# decoder.net
KiCad netlist of a schematic drawn in Altium Designer
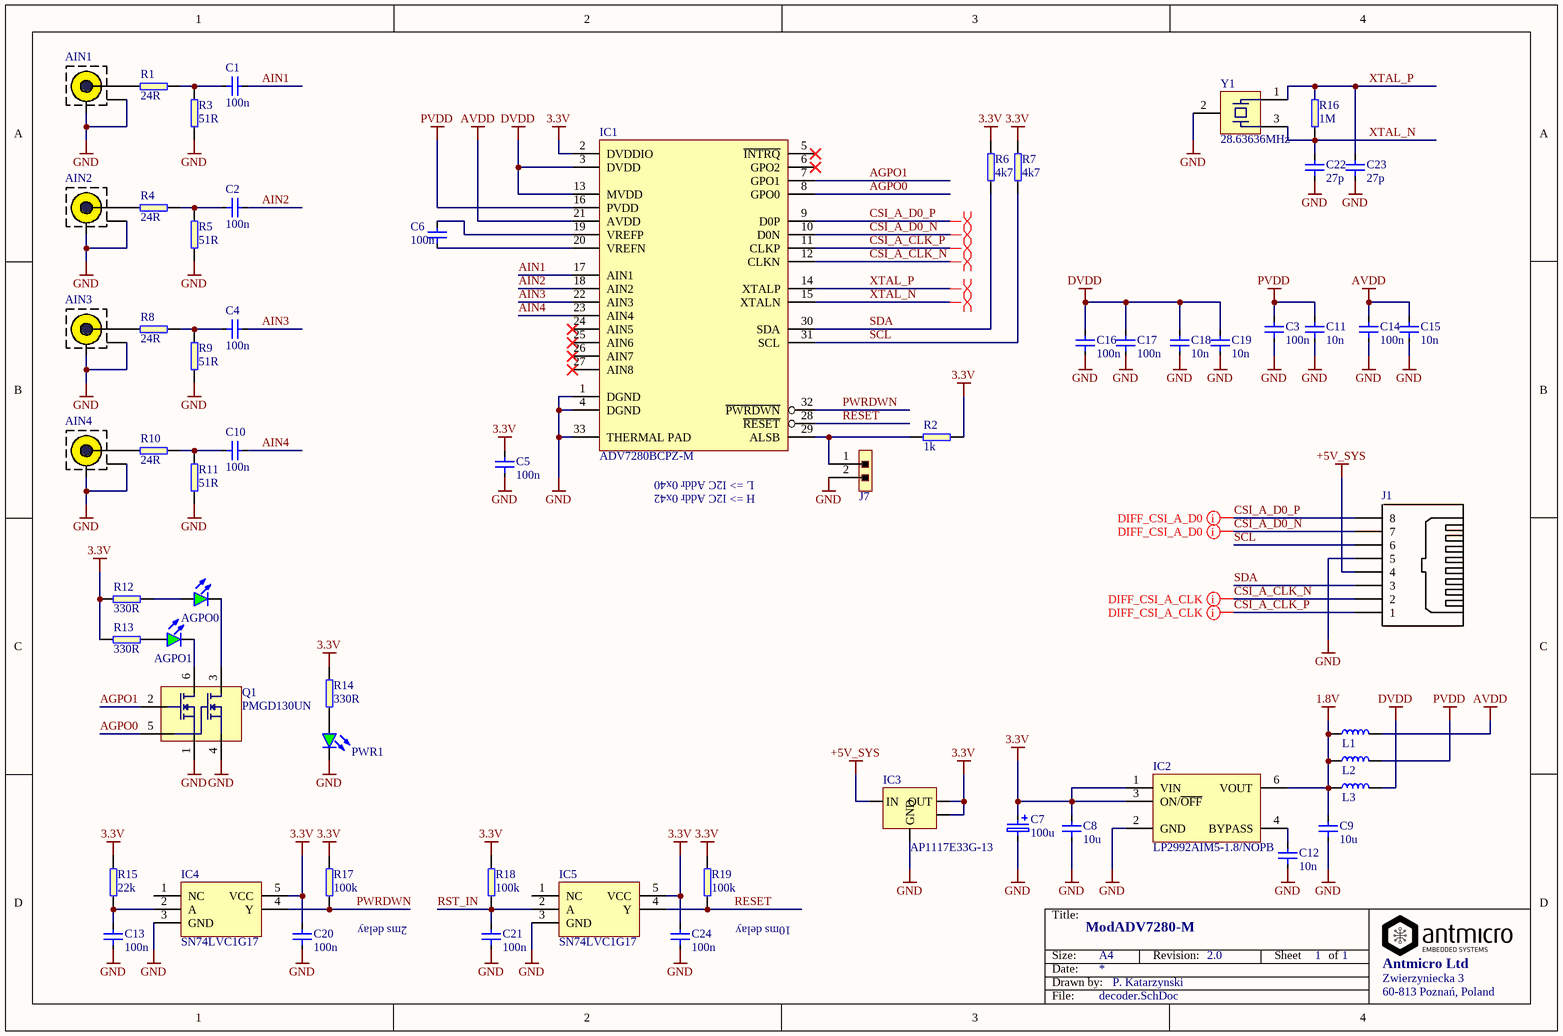
[diagram p0: decoder.SchDoc]

(export (version "E")
  (design (tool "Eeschema 10.0.6"))
  (components
    (comp (ref "AGPO0")
      (value "*")
      (footprint "LED0603")
      (description "LED Green 0603 case")
      (fields (field (name "PART NUMBER") "LED_G"))
      (libsource (lib "AntmicroComponents") (part "LED"))
    )
    (comp (ref "AGPO1")
      (value "*")
      (footprint "LED0603")
      (description "LED Green 0603 case")
      (fields (field (name "PART NUMBER") "LED_G"))
      (libsource (lib "AntmicroComponents") (part "LED"))
    )
    (comp (ref "AIN1")
      (value "~")
      (footprint "CC-134B")
      (description "Shielded RCA socket")
      (fields (field (name "PART NUMBER") "CC-134B"))
      (libsource (lib "AntmicroComponents") (part "CC-134B"))
    )
    (comp (ref "AIN2")
      (value "~")
      (footprint "CC-134B")
      (description "Shielded RCA socket")
      (fields (field (name "PART NUMBER") "CC-134B"))
      (libsource (lib "AntmicroComponents") (part "CC-134B"))
    )
    (comp (ref "AIN3")
      (value "~")
      (footprint "CC-134B")
      (description "Shielded RCA socket")
      (fields (field (name "PART NUMBER") "CC-134B"))
      (libsource (lib "AntmicroComponents") (part "CC-134B"))
    )
    (comp (ref "AIN4")
      (value "~")
      (footprint "CC-134B")
      (description "Shielded RCA socket")
      (fields (field (name "PART NUMBER") "CC-134B"))
      (libsource (lib "AntmicroComponents") (part "CC-134B"))
    )
    (comp (ref "C1")
      (value "100n")
      (footprint "0603")
      (description "MLCC SMT Capacitor 100nF 0603")
      (fields (field (name "PART NUMBER") "C_100n_0603") (field (name "TOLERANCE") "5%"))
      (libsource (lib "AntmicroComponents") (part "C"))
    )
    (comp (ref "C2")
      (value "100n")
      (footprint "0603")
      (description "MLCC SMT Capacitor 100nF 0603")
      (fields (field (name "PART NUMBER") "C_100n_0603") (field (name "TOLERANCE") "5%"))
      (libsource (lib "AntmicroComponents") (part "C"))
    )
    (comp (ref "C3")
      (value "100n")
      (footprint "0603")
      (description "MLCC SMT Capacitor 100nF 0603")
      (fields (field (name "PART NUMBER") "C_100n_0603") (field (name "TOLERANCE") "5%"))
      (libsource (lib "AntmicroComponents") (part "C"))
    )
    (comp (ref "C4")
      (value "100n")
      (footprint "0603")
      (description "MLCC SMT Capacitor 100nF 0603")
      (fields (field (name "PART NUMBER") "C_100n_0603") (field (name "TOLERANCE") "5%"))
      (libsource (lib "AntmicroComponents") (part "C"))
    )
    (comp (ref "C5")
      (value "100n")
      (footprint "0603")
      (description "MLCC SMT Capacitor 100nF 0603")
      (fields (field (name "PART NUMBER") "C_100n_0603") (field (name "TOLERANCE") "5%"))
      (libsource (lib "AntmicroComponents") (part "C"))
    )
    (comp (ref "C6")
      (value "100n")
      (footprint "0603")
      (description "MLCC SMT Capacitor 100nF 0603")
      (fields (field (name "PART NUMBER") "C_100n_0603") (field (name "TOLERANCE") "5%"))
      (libsource (lib "AntmicroComponents") (part "C"))
    )
    (comp (ref "C7")
      (value "100u")
      (footprint "KEMET_A")
      (description "Tantalum SMT Capacitor 100uF Case KEMET_A")
      (fields (field (name "PART NUMBER") "C_100u_KEMET_A"))
      (libsource (lib "AntmicroComponents") (part "CPol"))
    )
    (comp (ref "C8")
      (value "10u")
      (footprint "0603")
      (description "MLCC SMT Capacitor 10uF 0603")
      (fields (field (name "PART NUMBER") "C_10u_0603"))
      (libsource (lib "AntmicroComponents") (part "C"))
    )
    (comp (ref "C9")
      (value "10u")
      (footprint "0603")
      (description "MLCC SMT Capacitor 10uF 0603")
      (fields (field (name "PART NUMBER") "C_10u_0603"))
      (libsource (lib "AntmicroComponents") (part "C"))
    )
    (comp (ref "C10")
      (value "100n")
      (footprint "0603")
      (description "MLCC SMT Capacitor 100nF 0603")
      (fields (field (name "PART NUMBER") "C_100n_0603") (field (name "TOLERANCE") "5%"))
      (libsource (lib "AntmicroComponents") (part "C"))
    )
    (comp (ref "C11")
      (value "10n")
      (footprint "0603")
      (description "MLCC SMT Capacitor 10nF 0603")
      (fields (field (name "PART NUMBER") "C_10n_0603"))
      (libsource (lib "AntmicroComponents") (part "C"))
    )
    (comp (ref "C12")
      (value "10n")
      (footprint "0603")
      (description "MLCC SMT Capacitor 10nF 0603")
      (fields (field (name "PART NUMBER") "C_10n_0603"))
      (libsource (lib "AntmicroComponents") (part "C"))
    )
    (comp (ref "C13")
      (value "100n")
      (footprint "0603")
      (description "MLCC SMT Capacitor 100nF 0603")
      (fields (field (name "PART NUMBER") "C_100n_0603") (field (name "TOLERANCE") "5%"))
      (libsource (lib "AntmicroComponents") (part "C"))
    )
    (comp (ref "C14")
      (value "100n")
      (footprint "0603")
      (description "MLCC SMT Capacitor 100nF 0603")
      (fields (field (name "PART NUMBER") "C_100n_0603") (field (name "TOLERANCE") "5%"))
      (libsource (lib "AntmicroComponents") (part "C"))
    )
    (comp (ref "C15")
      (value "10n")
      (footprint "0603")
      (description "MLCC SMT Capacitor 10nF 0603")
      (fields (field (name "PART NUMBER") "C_10n_0603"))
      (libsource (lib "AntmicroComponents") (part "C"))
    )
    (comp (ref "C16")
      (value "100n")
      (footprint "0603")
      (description "MLCC SMT Capacitor 100nF 0603")
      (fields (field (name "PART NUMBER") "C_100n_0603") (field (name "TOLERANCE") "5%"))
      (libsource (lib "AntmicroComponents") (part "C"))
    )
    (comp (ref "C17")
      (value "100n")
      (footprint "0603")
      (description "MLCC SMT Capacitor 100nF 0603")
      (fields (field (name "PART NUMBER") "C_100n_0603") (field (name "TOLERANCE") "5%"))
      (libsource (lib "AntmicroComponents") (part "C"))
    )
    (comp (ref "C18")
      (value "10n")
      (footprint "0603")
      (description "MLCC SMT Capacitor 10nF 0603")
      (fields (field (name "PART NUMBER") "C_10n_0603"))
      (libsource (lib "AntmicroComponents") (part "C"))
    )
    (comp (ref "C19")
      (value "10n")
      (footprint "0603")
      (description "MLCC SMT Capacitor 10nF 0603")
      (fields (field (name "PART NUMBER") "C_10n_0603"))
      (libsource (lib "AntmicroComponents") (part "C"))
    )
    (comp (ref "C20")
      (value "100n")
      (footprint "0603")
      (description "MLCC SMT Capacitor 100nF 0603")
      (fields (field (name "PART NUMBER") "C_100n_0603") (field (name "TOLERANCE") "5%"))
      (libsource (lib "AntmicroComponents") (part "C"))
    )
    (comp (ref "C21")
      (value "100n")
      (footprint "0603")
      (description "MLCC SMT Capacitor 100nF 0603")
      (fields (field (name "PART NUMBER") "C_100n_0603") (field (name "TOLERANCE") "5%"))
      (libsource (lib "AntmicroComponents") (part "C"))
    )
    (comp (ref "C22")
      (value "27p")
      (footprint "0603")
      (description "MLCC SMT Capacitor 27pF 0603")
      (fields (field (name "PART NUMBER") "C_27p_0603"))
      (libsource (lib "AntmicroComponents") (part "C"))
    )
    (comp (ref "C23")
      (value "27p")
      (footprint "0603")
      (description "MLCC SMT Capacitor 27pF 0603")
      (fields (field (name "PART NUMBER") "C_27p_0603"))
      (libsource (lib "AntmicroComponents") (part "C"))
    )
    (comp (ref "C24")
      (value "100n")
      (footprint "0603")
      (description "MLCC SMT Capacitor 100nF 0603")
      (fields (field (name "PART NUMBER") "C_100n_0603") (field (name "TOLERANCE") "5%"))
      (libsource (lib "AntmicroComponents") (part "C"))
    )
    (comp (ref "IC1")
      (value "ADV7280BCPZ-M")
      (footprint "LFCSP-32")
      (description "MIPI 10Bit 4x Oversampled SDTV Video Decoder with Deinterlacer")
      (libsource (lib "AntmicroComponents") (part "ADV7280-M"))
    )
    (comp (ref "IC2")
      (value "LP2992AIM5-1.8/NOPB")
      (footprint "SOT23-5N")
      (description "LDO 1.8V 250mA")
      (fields (field (name "PART NUMBER") "LP2992AIM5-1.8"))
      (libsource (lib "AntmicroComponents") (part "LP2992AIM5-1.8"))
    )
    (comp (ref "IC3")
      (value "AP1117E33G-13")
      (footprint "SOT223")
      (description "IC, LDO, REG, 3.3V, SOT223")
      (libsource (lib "AntmicroComponents") (part "xx1117"))
    )
    (comp (ref "IC4")
      (value "SN74LVC1G17")
      (footprint "SOT23127P600-8N")
      (description "Single Schmitt trigger buffer")
      (libsource (lib "AntmicroComponents") (part "SN74LVC1G17"))
    )
    (comp (ref "IC5")
      (value "SN74LVC1G17")
      (footprint "SOT23127P600-8N")
      (description "Single Schmitt trigger buffer")
      (libsource (lib "AntmicroComponents") (part "SN74LVC1G17"))
    )
    (comp (ref "J1")
      (value "~")
      (footprint "RJ45 AMP-1-406541")
      (description "MODULAR, JACK, THT, R/A, RJ45, 8P8C")
      (fields (field (name "PART NUMBER") "RJ45 AMP-1-406541"))
      (libsource (lib "AntmicroComponents") (part "RJ45 AMP-1-406541"))
    )
    (comp (ref "J7")
      (value "*")
      (footprint "HEADER_1X2_male 2.54mm")
      (description "1x2 pinhead male")
      (fields (field (name "PART NUMBER") "HEADER_1X2_male"))
      (libsource (lib "AntmicroComponents") (part "HEADER_1X2_male"))
    )
    (comp (ref "L1")
      (value "*")
      (footprint "0805")
      (description "WURTH ELEKTRONIK - 742792022 - FERRITE BEAD, 0.05OHM, 2A, 0805")
      (fields (field (name "PART NUMBER") "742792022") (field (name "TOLERANCE") "25%"))
      (libsource (lib "AntmicroComponents") (part "Inductor SMT"))
    )
    (comp (ref "L2")
      (value "*")
      (footprint "0805")
      (description "WURTH ELEKTRONIK - 742792022 - FERRITE BEAD, 0.05OHM, 2A, 0805")
      (fields (field (name "PART NUMBER") "742792022") (field (name "TOLERANCE") "25%"))
      (libsource (lib "AntmicroComponents") (part "Inductor SMT"))
    )
    (comp (ref "L3")
      (value "*")
      (footprint "0805")
      (description "WURTH ELEKTRONIK - 742792022 - FERRITE BEAD, 0.05OHM, 2A, 0805")
      (fields (field (name "PART NUMBER") "742792022") (field (name "TOLERANCE") "25%"))
      (libsource (lib "AntmicroComponents") (part "Inductor SMT"))
    )
    (comp (ref "PWR1")
      (value "*")
      (footprint "LED0603")
      (description "LED Green 0603 case")
      (fields (field (name "PART NUMBER") "LED_G"))
      (libsource (lib "AntmicroComponents") (part "LED"))
    )
    (comp (ref "Q1")
      (value "PMGD130UN")
      (footprint "TSOP65P210X110-6N")
      (description "20 V, dual N-channel Trench MOSFET")
      (libsource (lib "AntmicroComponents") (part "PMGD130UN"))
    )
    (comp (ref "R1")
      (value "24R")
      (footprint "0603")
      (description "SMT Resistor 24R 0603")
      (fields (field (name "PART NUMBER") "R_24R_0603"))
      (libsource (lib "") (part "R_1"))
    )
    (comp (ref "R2")
      (value "1k")
      (footprint "0603")
      (description "SMT Resistor 1k 0603")
      (fields (field (name "PART NUMBER") "R_1k_0603") (field (name "TOLERANCE") "5%"))
      (libsource (lib "") (part "R_2"))
    )
    (comp (ref "R3")
      (value "51R")
      (footprint "0805")
      (description "SMT Resistor 51R 0805")
      (fields (field (name "PART NUMBER") "R_51R_0805") (field (name "TOLERANCE") "1%"))
      (libsource (lib "AntmicroComponents") (part "R"))
    )
    (comp (ref "R4")
      (value "24R")
      (footprint "0603")
      (description "SMT Resistor 24R 0603")
      (fields (field (name "PART NUMBER") "R_24R_0603"))
      (libsource (lib "") (part "R_1"))
    )
    (comp (ref "R5")
      (value "51R")
      (footprint "0805")
      (description "SMT Resistor 51R 0805")
      (fields (field (name "PART NUMBER") "R_51R_0805") (field (name "TOLERANCE") "1%"))
      (libsource (lib "AntmicroComponents") (part "R"))
    )
    (comp (ref "R6")
      (value "4k7")
      (footprint "0603")
      (description "SMT Resistor 4k7 0603")
      (fields (field (name "PART NUMBER") "R_4k7_0603"))
      (libsource (lib "AntmicroComponents") (part "R"))
    )
    (comp (ref "R7")
      (value "4k7")
      (footprint "0603")
      (description "SMT Resistor 4k7 0603")
      (fields (field (name "PART NUMBER") "R_4k7_0603"))
      (libsource (lib "AntmicroComponents") (part "R"))
    )
    (comp (ref "R8")
      (value "24R")
      (footprint "0603")
      (description "SMT Resistor 24R 0603")
      (fields (field (name "PART NUMBER") "R_24R_0603"))
      (libsource (lib "") (part "R_1"))
    )
    (comp (ref "R9")
      (value "51R")
      (footprint "0805")
      (description "SMT Resistor 51R 0805")
      (fields (field (name "PART NUMBER") "R_51R_0805") (field (name "TOLERANCE") "1%"))
      (libsource (lib "AntmicroComponents") (part "R"))
    )
    (comp (ref "R10")
      (value "24R")
      (footprint "0603")
      (description "SMT Resistor 24R 0603")
      (fields (field (name "PART NUMBER") "R_24R_0603"))
      (libsource (lib "") (part "R_1"))
    )
    (comp (ref "R11")
      (value "51R")
      (footprint "0805")
      (description "SMT Resistor 51R 0805")
      (fields (field (name "PART NUMBER") "R_51R_0805") (field (name "TOLERANCE") "1%"))
      (libsource (lib "AntmicroComponents") (part "R"))
    )
    (comp (ref "R12")
      (value "330R")
      (footprint "0603")
      (description "SMT Resistor 330R 0603")
      (fields (field (name "PART NUMBER") "R_330R_0603") (field (name "TOLERANCE") "5%"))
      (libsource (lib "") (part "R_2"))
    )
    (comp (ref "R13")
      (value "330R")
      (footprint "0603")
      (description "SMT Resistor 330R 0603")
      (fields (field (name "PART NUMBER") "R_330R_0603") (field (name "TOLERANCE") "5%"))
      (libsource (lib "") (part "R_2"))
    )
    (comp (ref "R14")
      (value "330R")
      (footprint "0603")
      (description "SMT Resistor 330R 0603")
      (fields (field (name "PART NUMBER") "R_330R_0603") (field (name "TOLERANCE") "5%"))
      (libsource (lib "AntmicroComponents") (part "R"))
    )
    (comp (ref "R15")
      (value "22k")
      (footprint "0603")
      (description "SMT Resistor 22k 0603")
      (fields (field (name "PART NUMBER") "R_22k_0603"))
      (libsource (lib "AntmicroComponents") (part "R"))
    )
    (comp (ref "R16")
      (value "1M")
      (footprint "0603")
      (description "SMT Resistor 1M 0603")
      (fields (field (name "PART NUMBER") "R_1M_0603"))
      (libsource (lib "AntmicroComponents") (part "R"))
    )
    (comp (ref "R17")
      (value "100k")
      (footprint "0603")
      (description "SMT Resistor 100k 0603")
      (fields (field (name "PART NUMBER") "R_100k_0603") (field (name "TOLERANCE") "5%"))
      (libsource (lib "AntmicroComponents") (part "R"))
    )
    (comp (ref "R18")
      (value "100k")
      (footprint "0603")
      (description "SMT Resistor 100k 0603")
      (fields (field (name "PART NUMBER") "R_100k_0603") (field (name "TOLERANCE") "5%"))
      (libsource (lib "AntmicroComponents") (part "R"))
    )
    (comp (ref "R19")
      (value "100k")
      (footprint "0603")
      (description "SMT Resistor 100k 0603")
      (fields (field (name "PART NUMBER") "R_100k_0603") (field (name "TOLERANCE") "5%"))
      (libsource (lib "AntmicroComponents") (part "R"))
    )
    (comp (ref "Y1")
      (value "28.63636MHz")
      (footprint "TXC_7B")
      (description "TXC  7B-28.63636MAAJ-T  XTAL, 28.63636MHZ, 18PF, SMD, 5X3.2")
      (fields (field (name "PART NUMBER") "7B-28.63636MAAJ-T"))
      (libsource (lib "AntmicroComponents") (part "TXC_7B"))
    )
  )
  (nets
    (net (code "1") (name "+5V_SYS") (class "Default")
      (node (ref "IC3") (pin "3") (pinfunction "IN_3") (pintype "power_in"))
      (node (ref "J1") (pin "4") (pinfunction "4_4") (pintype "passive"))
    )
    (net (code "2") (name "/AGPO0") (class "Default")
      (node (ref "IC1") (pin "8") (pinfunction "GPO0_8") (pintype "passive"))
      (node (ref "Q1") (pin "5") (pinfunction "G2_5") (pintype "passive"))
    )
    (net (code "3") (name "/AGPO1") (class "Default")
      (node (ref "IC1") (pin "7") (pinfunction "GPO1_7") (pintype "passive"))
      (node (ref "Q1") (pin "2") (pinfunction "G1_2") (pintype "passive"))
    )
    (net (code "4") (name "/AIN1") (class "Default")
      (node (ref "C1") (pin "2") (pinfunction "2_2") (pintype "passive"))
      (node (ref "IC1") (pin "17") (pinfunction "AIN1_17") (pintype "passive"))
    )
    (net (code "5") (name "/AIN2") (class "Default")
      (node (ref "C2") (pin "2") (pinfunction "2_2") (pintype "passive"))
      (node (ref "IC1") (pin "18") (pinfunction "AIN2_18") (pintype "passive"))
    )
    (net (code "6") (name "/AIN3") (class "Default")
      (node (ref "C4") (pin "2") (pinfunction "2_2") (pintype "passive"))
      (node (ref "IC1") (pin "22") (pinfunction "AIN3_22") (pintype "passive"))
    )
    (net (code "7") (name "/AIN4") (class "Default")
      (node (ref "C10") (pin "2") (pinfunction "2_2") (pintype "passive"))
      (node (ref "IC1") (pin "23") (pinfunction "AIN4_23") (pintype "passive"))
    )
    (net (code "8") (name "/CSI_A_CLK_N") (class "Default")
      (node (ref "IC1") (pin "12") (pinfunction "CLKN_12") (pintype "passive"))
      (node (ref "J1") (pin "2") (pinfunction "2_2") (pintype "passive"))
    )
    (net (code "9") (name "/CSI_A_CLK_P") (class "Default")
      (node (ref "IC1") (pin "11") (pinfunction "CLKP_11") (pintype "passive"))
      (node (ref "J1") (pin "1") (pinfunction "1_1") (pintype "passive"))
    )
    (net (code "10") (name "/CSI_A_D0_N") (class "Default")
      (node (ref "IC1") (pin "10") (pinfunction "D0N_10") (pintype "passive"))
      (node (ref "J1") (pin "7") (pinfunction "7_7") (pintype "passive"))
    )
    (net (code "11") (name "/CSI_A_D0_P") (class "Default")
      (node (ref "IC1") (pin "9") (pinfunction "D0P_9") (pintype "passive"))
      (node (ref "J1") (pin "8") (pinfunction "8_8") (pintype "passive"))
    )
    (net (code "12") (name "/PWRDWN") (class "Default")
      (node (ref "IC1") (pin "32") (pinfunction "~{PWRDWN}_32") (pintype "passive"))
      (node (ref "IC4") (pin "4") (pinfunction "Y_4") (pintype "passive"))
      (node (ref "R17") (pin "1") (pintype "passive"))
    )
    (net (code "13") (name "/RESET") (class "Default")
      (node (ref "IC1") (pin "28") (pinfunction "~{RESET}_28") (pintype "passive"))
      (node (ref "IC5") (pin "4") (pinfunction "Y_4") (pintype "passive"))
      (node (ref "R19") (pin "1") (pintype "passive"))
    )
    (net (code "14") (name "/RST_IN") (class "Default")
      (node (ref "C21") (pin "2") (pinfunction "2_2") (pintype "passive"))
      (node (ref "IC5") (pin "2") (pinfunction "A_2") (pintype "passive"))
      (node (ref "R18") (pin "1") (pintype "passive"))
    )
    (net (code "15") (name "/SCL") (class "Default")
      (node (ref "IC1") (pin "31") (pinfunction "SCL_31") (pintype "passive"))
      (node (ref "J1") (pin "6") (pinfunction "6_6") (pintype "passive"))
      (node (ref "R7") (pin "1") (pintype "passive"))
    )
    (net (code "16") (name "/SDA") (class "Default")
      (node (ref "IC1") (pin "30") (pinfunction "SDA_30") (pintype "passive"))
      (node (ref "J1") (pin "3") (pinfunction "3_3") (pintype "passive"))
      (node (ref "R6") (pin "1") (pintype "passive"))
    )
    (net (code "17") (name "/XTAL_N") (class "Default")
      (node (ref "C22") (pin "2") (pinfunction "2_2") (pintype "passive"))
      (node (ref "IC1") (pin "15") (pinfunction "XTALN_15") (pintype "passive"))
      (node (ref "R16") (pin "1") (pintype "passive"))
      (node (ref "Y1") (pin "3") (pinfunction "XTAL2_3") (pintype "passive"))
    )
    (net (code "18") (name "/XTAL_P") (class "Default")
      (node (ref "C23") (pin "2") (pinfunction "2_2") (pintype "passive"))
      (node (ref "IC1") (pin "14") (pinfunction "XTALP_14") (pintype "passive"))
      (node (ref "R16") (pin "2") (pintype "passive"))
      (node (ref "Y1") (pin "1") (pinfunction "XTAL1_1") (pintype "passive"))
    )
    (net (code "19") (name "1.8V") (class "Default")
      (node (ref "C9") (pin "2") (pinfunction "2_2") (pintype "passive"))
      (node (ref "IC2") (pin "6") (pinfunction "VOUT_6") (pintype "passive"))
      (node (ref "L1") (pin "1") (pintype "passive"))
      (node (ref "L2") (pin "1") (pintype "passive"))
      (node (ref "L3") (pin "1") (pintype "passive"))
    )
    (net (code "20") (name "3.3V") (class "Default")
      (node (ref "C20") (pin "2") (pinfunction "2_2") (pintype "passive"))
      (node (ref "C24") (pin "2") (pinfunction "2_2") (pintype "passive"))
      (node (ref "C5") (pin "2") (pinfunction "2_2") (pintype "passive"))
      (node (ref "C7") (pin "1") (pinfunction "1_1") (pintype "passive"))
      (node (ref "C8") (pin "2") (pinfunction "2_2") (pintype "passive"))
      (node (ref "IC1") (pin "2") (pinfunction "DVDDIO_2") (pintype "passive"))
      (node (ref "IC2") (pin "1") (pinfunction "VIN_1") (pintype "passive"))
      (node (ref "IC2") (pin "3") (pinfunction "ON/~{OFF}_3") (pintype "passive"))
      (node (ref "IC3") (pin "2") (pinfunction "OUT_2") (pintype "passive"))
      (node (ref "IC3") (pin "4") (pinfunction "OUT_4") (pintype "passive"))
      (node (ref "IC4") (pin "5") (pinfunction "VCC_5") (pintype "passive"))
      (node (ref "IC5") (pin "5") (pinfunction "VCC_5") (pintype "passive"))
      (node (ref "R12") (pin "2") (pintype "passive"))
      (node (ref "R13") (pin "2") (pintype "passive"))
      (node (ref "R14") (pin "2") (pintype "passive"))
      (node (ref "R15") (pin "2") (pintype "passive"))
      (node (ref "R17") (pin "2") (pintype "passive"))
      (node (ref "R18") (pin "2") (pintype "passive"))
      (node (ref "R19") (pin "2") (pintype "passive"))
      (node (ref "R2") (pin "1") (pintype "passive"))
      (node (ref "R6") (pin "2") (pintype "passive"))
      (node (ref "R7") (pin "2") (pintype "passive"))
    )
    (net (code "21") (name "AVDD") (class "Default")
      (node (ref "C14") (pin "2") (pinfunction "2_2") (pintype "passive"))
      (node (ref "C15") (pin "2") (pinfunction "2_2") (pintype "passive"))
      (node (ref "IC1") (pin "21") (pinfunction "AVDD_21") (pintype "passive"))
      (node (ref "L1") (pin "2") (pintype "passive"))
    )
    (net (code "22") (name "DVDD") (class "Default")
      (node (ref "C16") (pin "2") (pinfunction "2_2") (pintype "passive"))
      (node (ref "C17") (pin "2") (pinfunction "2_2") (pintype "passive"))
      (node (ref "C18") (pin "2") (pinfunction "2_2") (pintype "passive"))
      (node (ref "C19") (pin "2") (pinfunction "2_2") (pintype "passive"))
      (node (ref "IC1") (pin "13") (pinfunction "MVDD_13") (pintype "passive"))
      (node (ref "IC1") (pin "3") (pinfunction "DVDD_3") (pintype "passive"))
      (node (ref "L3") (pin "2") (pintype "passive"))
    )
    (net (code "23") (name "GND") (class "Default")
      (node (ref "AIN1") (pin "GND") (pinfunction "GND_GND") (pintype "passive"))
      (node (ref "AIN1") (pin "SHIELD") (pinfunction "SHIELD_SHIELD") (pintype "passive"))
      (node (ref "AIN2") (pin "GND") (pinfunction "GND_GND") (pintype "passive"))
      (node (ref "AIN2") (pin "SHIELD") (pinfunction "SHIELD_SHIELD") (pintype "passive"))
      (node (ref "AIN3") (pin "GND") (pinfunction "GND_GND") (pintype "passive"))
      (node (ref "AIN3") (pin "SHIELD") (pinfunction "SHIELD_SHIELD") (pintype "passive"))
      (node (ref "AIN4") (pin "GND") (pinfunction "GND_GND") (pintype "passive"))
      (node (ref "AIN4") (pin "SHIELD") (pinfunction "SHIELD_SHIELD") (pintype "passive"))
      (node (ref "C11") (pin "1") (pinfunction "1_1") (pintype "passive"))
      (node (ref "C12") (pin "1") (pinfunction "1_1") (pintype "passive"))
      (node (ref "C13") (pin "1") (pinfunction "1_1") (pintype "passive"))
      (node (ref "C14") (pin "1") (pinfunction "1_1") (pintype "passive"))
      (node (ref "C15") (pin "1") (pinfunction "1_1") (pintype "passive"))
      (node (ref "C16") (pin "1") (pinfunction "1_1") (pintype "passive"))
      (node (ref "C17") (pin "1") (pinfunction "1_1") (pintype "passive"))
      (node (ref "C18") (pin "1") (pinfunction "1_1") (pintype "passive"))
      (node (ref "C19") (pin "1") (pinfunction "1_1") (pintype "passive"))
      (node (ref "C20") (pin "1") (pinfunction "1_1") (pintype "passive"))
      (node (ref "C21") (pin "1") (pinfunction "1_1") (pintype "passive"))
      (node (ref "C22") (pin "1") (pinfunction "1_1") (pintype "passive"))
      (node (ref "C23") (pin "1") (pinfunction "1_1") (pintype "passive"))
      (node (ref "C24") (pin "1") (pinfunction "1_1") (pintype "passive"))
      (node (ref "C3") (pin "1") (pinfunction "1_1") (pintype "passive"))
      (node (ref "C5") (pin "1") (pinfunction "1_1") (pintype "passive"))
      (node (ref "C7") (pin "2") (pinfunction "2_2") (pintype "passive"))
      (node (ref "C8") (pin "1") (pinfunction "1_1") (pintype "passive"))
      (node (ref "C9") (pin "1") (pinfunction "1_1") (pintype "passive"))
      (node (ref "IC1") (pin "1") (pinfunction "DGND_1") (pintype "passive"))
      (node (ref "IC1") (pin "33") (pinfunction "THERMAL_PAD_33") (pintype "passive"))
      (node (ref "IC1") (pin "4") (pinfunction "DGND_4") (pintype "passive"))
      (node (ref "IC2") (pin "2") (pinfunction "GND_2") (pintype "passive"))
      (node (ref "IC3") (pin "1") (pinfunction "GND_1") (pintype "power_in"))
      (node (ref "IC4") (pin "3") (pinfunction "GND_3") (pintype "passive"))
      (node (ref "IC5") (pin "3") (pinfunction "GND_3") (pintype "passive"))
      (node (ref "J1") (pin "5") (pinfunction "5_5") (pintype "passive"))
      (node (ref "J7") (pin "2") (pinfunction "2_2") (pintype "passive"))
      (node (ref "PWR1") (pin "K") (pinfunction "K_K") (pintype "passive"))
      (node (ref "Q1") (pin "1") (pinfunction "S1_1") (pintype "passive"))
      (node (ref "Q1") (pin "4") (pinfunction "S2_4") (pintype "passive"))
      (node (ref "R11") (pin "1") (pintype "passive"))
      (node (ref "R3") (pin "1") (pintype "passive"))
      (node (ref "R5") (pin "1") (pintype "passive"))
      (node (ref "R9") (pin "1") (pintype "passive"))
      (node (ref "Y1") (pin "2") (pinfunction "GND_2") (pintype "passive"))
    )
    (net (code "24") (name "Net-(AGPO0-PadA)") (class "Default")
      (node (ref "AGPO0") (pin "A") (pinfunction "A_A") (pintype "passive"))
      (node (ref "R12") (pin "1") (pintype "passive"))
    )
    (net (code "25") (name "Net-(AGPO1-PadA)") (class "Default")
      (node (ref "AGPO1") (pin "A") (pinfunction "A_A") (pintype "passive"))
      (node (ref "R13") (pin "1") (pintype "passive"))
    )
    (net (code "26") (name "Net-(AIN1-PadSIGNAL)") (class "Default")
      (node (ref "AIN1") (pin "SIGNAL") (pinfunction "SIGNAL_SIGNAL") (pintype "passive"))
      (node (ref "R1") (pin "1") (pintype "passive"))
    )
    (net (code "27") (name "Net-(AIN2-PadSIGNAL)") (class "Default")
      (node (ref "AIN2") (pin "SIGNAL") (pinfunction "SIGNAL_SIGNAL") (pintype "passive"))
      (node (ref "R4") (pin "1") (pintype "passive"))
    )
    (net (code "28") (name "Net-(AIN3-PadSIGNAL)") (class "Default")
      (node (ref "AIN3") (pin "SIGNAL") (pinfunction "SIGNAL_SIGNAL") (pintype "passive"))
      (node (ref "R8") (pin "1") (pintype "passive"))
    )
    (net (code "29") (name "Net-(AIN4-PadSIGNAL)") (class "Default")
      (node (ref "AIN4") (pin "SIGNAL") (pinfunction "SIGNAL_SIGNAL") (pintype "passive"))
      (node (ref "R10") (pin "1") (pintype "passive"))
    )
    (net (code "30") (name "Net-(C1-Pad1)") (class "Default")
      (node (ref "C1") (pin "1") (pinfunction "1_1") (pintype "passive"))
      (node (ref "R1") (pin "2") (pintype "passive"))
      (node (ref "R3") (pin "2") (pintype "passive"))
    )
    (net (code "31") (name "Net-(C2-Pad1)") (class "Default")
      (node (ref "C2") (pin "1") (pinfunction "1_1") (pintype "passive"))
      (node (ref "R4") (pin "2") (pintype "passive"))
      (node (ref "R5") (pin "2") (pintype "passive"))
    )
    (net (code "32") (name "Net-(C4-Pad1)") (class "Default")
      (node (ref "C4") (pin "1") (pinfunction "1_1") (pintype "passive"))
      (node (ref "R8") (pin "2") (pintype "passive"))
      (node (ref "R9") (pin "2") (pintype "passive"))
    )
    (net (code "33") (name "Net-(C10-Pad1)") (class "Default")
      (node (ref "C10") (pin "1") (pinfunction "1_1") (pintype "passive"))
      (node (ref "R10") (pin "2") (pintype "passive"))
      (node (ref "R11") (pin "2") (pintype "passive"))
    )
    (net (code "34") (name "Net-(IC1-ALSB)") (class "Default")
      (node (ref "IC1") (pin "29") (pinfunction "ALSB_29") (pintype "passive"))
      (node (ref "J7") (pin "1") (pinfunction "1_1") (pintype "passive"))
      (node (ref "R2") (pin "2") (pintype "passive"))
    )
    (net (code "35") (name "Net-(IC1-VREFN)") (class "Default")
      (node (ref "C6") (pin "1") (pinfunction "1_1") (pintype "passive"))
      (node (ref "IC1") (pin "20") (pinfunction "VREFN_20") (pintype "passive"))
    )
    (net (code "36") (name "Net-(IC1-VREFP)") (class "Default")
      (node (ref "C6") (pin "2") (pinfunction "2_2") (pintype "passive"))
      (node (ref "IC1") (pin "19") (pinfunction "VREFP_19") (pintype "passive"))
    )
    (net (code "37") (name "Net-(IC2-BYPASS)") (class "Default")
      (node (ref "C12") (pin "2") (pinfunction "2_2") (pintype "passive"))
      (node (ref "IC2") (pin "4") (pinfunction "BYPASS_4") (pintype "passive"))
    )
    (net (code "38") (name "Net-(IC4-A)") (class "Default")
      (node (ref "C13") (pin "2") (pinfunction "2_2") (pintype "passive"))
      (node (ref "IC4") (pin "2") (pinfunction "A_2") (pintype "passive"))
      (node (ref "R15") (pin "1") (pintype "passive"))
    )
    (net (code "39") (name "Net-(PWR1-PadA)") (class "Default")
      (node (ref "PWR1") (pin "A") (pinfunction "A_A") (pintype "passive"))
      (node (ref "R14") (pin "1") (pintype "passive"))
    )
    (net (code "40") (name "Net-(Q1-D1)") (class "Default")
      (node (ref "AGPO1") (pin "K") (pinfunction "K_K") (pintype "passive"))
      (node (ref "Q1") (pin "6") (pinfunction "D1_6") (pintype "passive"))
    )
    (net (code "41") (name "Net-(Q1-D2)") (class "Default")
      (node (ref "AGPO0") (pin "K") (pinfunction "K_K") (pintype "passive"))
      (node (ref "Q1") (pin "3") (pinfunction "D2_3") (pintype "passive"))
    )
    (net (code "42") (name "PVDD") (class "Default")
      (node (ref "C11") (pin "2") (pinfunction "2_2") (pintype "passive"))
      (node (ref "C3") (pin "2") (pinfunction "2_2") (pintype "passive"))
      (node (ref "IC1") (pin "16") (pinfunction "PVDD_16") (pintype "passive"))
      (node (ref "L2") (pin "2") (pintype "passive"))
    )
    (net (code "43") (name "unconnected-(IC1-AIN5-Pad24)") (class "Default")
      (node (ref "IC1") (pin "24") (pinfunction "AIN5_24") (pintype "passive+no_connect"))
    )
    (net (code "44") (name "unconnected-(IC1-AIN6-Pad25)") (class "Default")
      (node (ref "IC1") (pin "25") (pinfunction "AIN6_25") (pintype "passive+no_connect"))
    )
    (net (code "45") (name "unconnected-(IC1-AIN7-Pad26)") (class "Default")
      (node (ref "IC1") (pin "26") (pinfunction "AIN7_26") (pintype "passive+no_connect"))
    )
    (net (code "46") (name "unconnected-(IC1-AIN8-Pad27)") (class "Default")
      (node (ref "IC1") (pin "27") (pinfunction "AIN8_27") (pintype "passive+no_connect"))
    )
    (net (code "47") (name "unconnected-(IC1-GPO2-Pad6)") (class "Default")
      (node (ref "IC1") (pin "6") (pinfunction "GPO2_6") (pintype "passive+no_connect"))
    )
    (net (code "48") (name "unconnected-(IC1-~{INTRQ}-Pad5)") (class "Default")
      (node (ref "IC1") (pin "5") (pinfunction "~{INTRQ}_5") (pintype "passive+no_connect"))
    )
    (net (code "49") (name "unconnected-(IC4-NC-Pad1)") (class "Default")
      (node (ref "IC4") (pin "1") (pinfunction "NC_1") (pintype "passive"))
    )
    (net (code "50") (name "unconnected-(IC5-NC-Pad1)") (class "Default")
      (node (ref "IC5") (pin "1") (pinfunction "NC_1") (pintype "passive"))
    )
  )
)
